# Preamp.net
KiCad netlist of a schematic drawn in Altium Designer
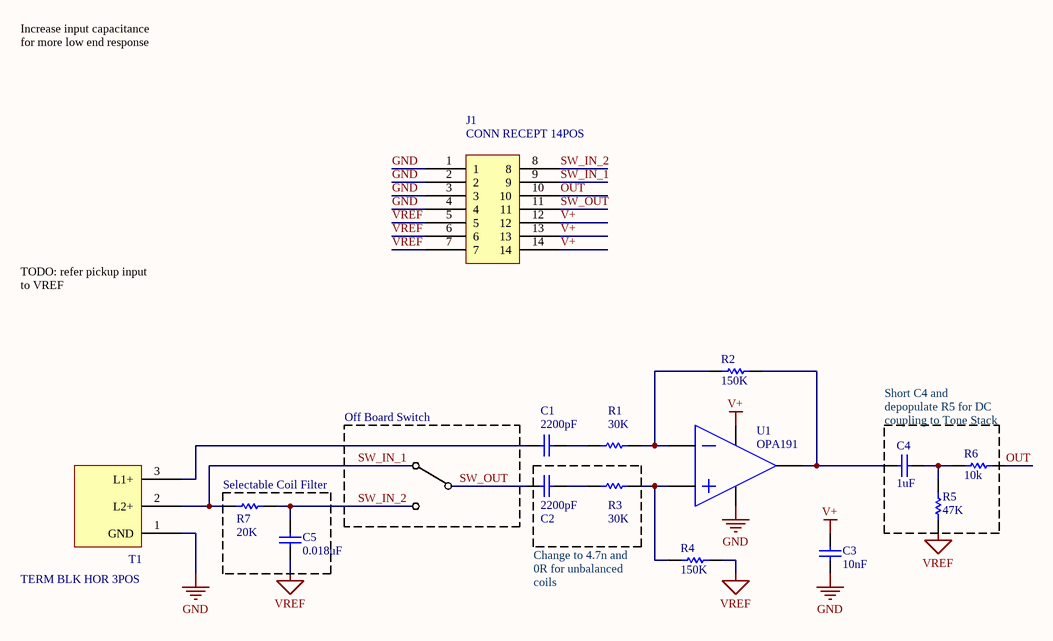
[diagram p0: Preamp.SchDoc]

(export (version "E")
  (design (tool "Eeschema 10.0.6"))
  (components
    (comp (ref "C1")
      (value "2200pF")
      (footprint "CAPC1608X09N")
      (description "2200pF ±1% 50V Ceramic Capacitor C0G, NP0 0603 (1608 Metric)")
      (fields (field (name "DIGIKEY PART NUMBER") "490-7768-1-ND") (field (name "MANUFACTURER") "Murata"))
      (libsource (lib "GuitarLibrary") (part "CAP CER 2200PF 50V C0G/NP0 0603"))
    )
    (comp (ref "C2")
      (value "2200pF")
      (footprint "CAPC1608X09N")
      (description "2200pF ±1% 50V Ceramic Capacitor C0G, NP0 0603 (1608 Metric)")
      (fields (field (name "DIGIKEY PART NUMBER") "490-7768-1-ND") (field (name "MANUFACTURER") "Murata"))
      (libsource (lib "GuitarLibrary") (part "CAP CER 2200PF 50V C0G/NP0 0603"))
    )
    (comp (ref "C3")
      (value "10nF")
      (footprint "CAPC1608X09N")
      (description "10000pF ±5% 50V Ceramic Capacitor C0G, NP0 0603 (1608 Metric)")
      (fields (field (name "DIGIKEY PART NUMBER") "490-9666-1-ND") (field (name "MANUFACTURER") "Murata"))
      (libsource (lib "GuitarLibrary") (part "CAP CER 10000PF 50V C0G/NP0 0603"))
    )
    (comp (ref "C4")
      (value "1uF")
      (footprint "CAPC1608X09N")
      (description "1µF ±10% 25V Ceramic Capacitor X7R 0603 (1608 Metric)")
      (fields (field (name "DIGIKEY PART NUMBER") "490-10673-1-ND") (field (name "VOLTAGE") "25V"))
      (libsource (lib "GuitarLibrary") (part "CAP CER 1UF 25V X7R 0603"))
    )
    (comp (ref "C5")
      (value "0.018uF")
      (footprint "CAPC1608X09N")
      (description "CAP CER 0.018UF 35V NP0 0603")
      (fields (field (name "DIGIKEY PART NUMBER") "445-174558-1-ND") (field (name "VOLTAGE") "35V"))
      (libsource (lib "GuitarLibrary") (part "CAP CER 0.018UF 35V NP0 0603"))
    )
    (comp (ref "J1")
      (value "CONN RECEPT 14POS")
      (footprint "DF12(3.0)-14DS")
      (description "14 Position Connector Header, Outer Shroud Contacts Surface Mount Gold")
      (libsource (lib "GuitarLibrary") (part "DF12(3.0)-14DS-0.5V(86)"))
    )
    (comp (ref "R1")
      (value "30K")
      (footprint "RESC1608X06N")
      (description "RES SMD 30K OHM 1% 1/10W 0603")
      (fields (field (name "TOLERANCE") "1%") (field (name "DIGIKEY PART NUMBER") "311-30.0KHRCT-ND"))
      (libsource (lib "GuitarLibrary") (part "RES SMD 30K OHM 1% 1/10W 0603"))
    )
    (comp (ref "R2")
      (value "150K")
      (footprint "RESC1608X06N")
      (description "RES SMD 150K OHM 1% 1/10W 0603")
      (fields (field (name "TOLERANCE") "1%") (field (name "DIGIKEY PART NUMBER") "311-150KHRCT-ND"))
      (libsource (lib "GuitarLibrary") (part "RES SMD 150K OHM 1% 1/10W 0603"))
    )
    (comp (ref "R3")
      (value "30K")
      (footprint "RESC1608X06N")
      (description "RES SMD 30K OHM 1% 1/10W 0603")
      (fields (field (name "TOLERANCE") "1%") (field (name "DIGIKEY PART NUMBER") "311-30.0KHRCT-ND"))
      (libsource (lib "GuitarLibrary") (part "RES SMD 30K OHM 1% 1/10W 0603"))
    )
    (comp (ref "R4")
      (value "150K")
      (footprint "RESC1608X06N")
      (description "RES SMD 150K OHM 1% 1/10W 0603")
      (fields (field (name "TOLERANCE") "1%") (field (name "DIGIKEY PART NUMBER") "311-150KHRCT-ND"))
      (libsource (lib "GuitarLibrary") (part "RES SMD 150K OHM 1% 1/10W 0603"))
    )
    (comp (ref "R5")
      (value "47K")
      (footprint "RESC1608X06N")
      (description "RES 47K 0603")
      (fields (field (name "TOLERANCE") "1%") (field (name "DIGIKEY PART NUMBER") "311-47.0KHRCT-ND"))
      (libsource (lib "GuitarLibrary") (part "RES SMD 47K OHM 1% 1/10W 0603"))
    )
    (comp (ref "R6")
      (value "10k")
      (footprint "RESC1608X06N")
      (description "RES SMD 10K OHM 1% 1/10W 0603")
      (fields (field (name "TOLERANCE") "1%") (field (name "POWER") "0.1W"))
      (libsource (lib "GuitarLibrary") (part "RES SMD 10K OHM 1% 1/10W 0603"))
    )
    (comp (ref "R7")
      (value "20K")
      (footprint "RESC1608X06N")
      (description "RES SMD 20K OHM 1% 1/10W 0603")
      (fields (field (name "TOLERANCE") "1%") (field (name "DIGIKEY PART NUMBER") "311-20.0KHRCT-ND"))
      (libsource (lib "GuitarLibrary") (part "RES SMD 20K OHM 1% 1/10W 0603"))
    )
    (comp (ref "T1")
      (value "TERM BLK HOR 3POS")
      (footprint "TERM BLK HOR 3POS")
      (description "3 Position Wire to Board Terminal Block Horizontal with Board 0.100\" (2.54mm) Surface Mount")
      (fields (field (name "DIGIKEY PART NUMBER") "1195-3657-1-ND"))
      (libsource (lib "GuitarLibrary") (part "TERM BLK HOR 3POS"))
    )
    (comp (ref "U1")
      (value "OPA191")
      (footprint "SOT23-5")
      (description "General Purpose Amplifier 1 Circuit Rail-to-Rail SOT-23-5")
      (fields (field (name "DIGIKEY PART NUMBER") "296-44386-1-ND"))
      (libsource (lib "GuitarLibrary") (part "OPA191IDBVR"))
    )
  )
  (nets
    (net (code "1") (name "/OUT") (class "Default")
      (node (ref "J1") (pin "10") (pinfunction "10_10") (pintype "passive"))
      (node (ref "R6") (pin "1") (pinfunction "1_1") (pintype "passive"))
    )
    (net (code "2") (name "/SW_IN_1") (class "Default")
      (node (ref "J1") (pin "9") (pinfunction "9_9") (pintype "passive"))
      (node (ref "R7") (pin "1") (pinfunction "1_1") (pintype "passive"))
      (node (ref "T1") (pin "2") (pinfunction "L2+_2") (pintype "passive"))
    )
    (net (code "3") (name "/SW_IN_2") (class "Default")
      (node (ref "C5") (pin "2") (pinfunction "2_2") (pintype "passive"))
      (node (ref "J1") (pin "8") (pinfunction "8_8") (pintype "passive"))
      (node (ref "R7") (pin "2") (pinfunction "2_2") (pintype "passive"))
    )
    (net (code "4") (name "/SW_OUT") (class "Default")
      (node (ref "C2") (pin "1") (pinfunction "1_1") (pintype "passive"))
      (node (ref "J1") (pin "11") (pinfunction "11_11") (pintype "passive"))
    )
    (net (code "5") (name "GND") (class "Default")
      (node (ref "C3") (pin "1") (pinfunction "1_1") (pintype "passive"))
      (node (ref "J1") (pin "1") (pinfunction "1_1") (pintype "passive"))
      (node (ref "J1") (pin "2") (pinfunction "2_2") (pintype "passive"))
      (node (ref "J1") (pin "3") (pinfunction "3_3") (pintype "passive"))
      (node (ref "J1") (pin "4") (pinfunction "4_4") (pintype "passive"))
      (node (ref "T1") (pin "1") (pinfunction "GND_1") (pintype "passive"))
      (node (ref "U1") (pin "2") (pinfunction "GND_2") (pintype "power_in"))
    )
    (net (code "6") (name "Net-(C1-Pad2)") (class "Default")
      (node (ref "C1") (pin "2") (pinfunction "2_2") (pintype "passive"))
      (node (ref "R1") (pin "1") (pinfunction "1_1") (pintype "passive"))
    )
    (net (code "7") (name "Net-(C2-Pad2)") (class "Default")
      (node (ref "C2") (pin "2") (pinfunction "2_2") (pintype "passive"))
      (node (ref "R3") (pin "1") (pinfunction "1_1") (pintype "passive"))
    )
    (net (code "8") (name "Net-(C4-Pad2)") (class "Default")
      (node (ref "C4") (pin "2") (pinfunction "2_2") (pintype "passive"))
      (node (ref "R5") (pin "2") (pinfunction "2_2") (pintype "passive"))
      (node (ref "R6") (pin "2") (pinfunction "2_2") (pintype "passive"))
    )
    (net (code "9") (name "Net-(T1-L1+)") (class "Default")
      (node (ref "C1") (pin "1") (pinfunction "1_1") (pintype "passive"))
      (node (ref "T1") (pin "3") (pinfunction "L1+_3") (pintype "passive"))
    )
    (net (code "10") (name "Net-(U1-VIN+)") (class "Default")
      (node (ref "R3") (pin "2") (pinfunction "2_2") (pintype "passive"))
      (node (ref "R4") (pin "1") (pinfunction "1_1") (pintype "passive"))
      (node (ref "U1") (pin "3") (pinfunction "VIN+_3") (pintype "passive"))
    )
    (net (code "11") (name "Net-(U1-VIN-)") (class "Default")
      (node (ref "R1") (pin "2") (pinfunction "2_2") (pintype "passive"))
      (node (ref "R2") (pin "1") (pinfunction "1_1") (pintype "passive"))
      (node (ref "U1") (pin "4") (pinfunction "VIN-_4") (pintype "passive"))
    )
    (net (code "12") (name "Net-(U1-VOUT)") (class "Default")
      (node (ref "C4") (pin "1") (pinfunction "1_1") (pintype "passive"))
      (node (ref "R2") (pin "2") (pinfunction "2_2") (pintype "passive"))
      (node (ref "U1") (pin "1") (pinfunction "VOUT_1") (pintype "passive"))
    )
    (net (code "13") (name "V+") (class "Default")
      (node (ref "C3") (pin "2") (pinfunction "2_2") (pintype "passive"))
      (node (ref "J1") (pin "12") (pinfunction "12_12") (pintype "passive"))
      (node (ref "J1") (pin "13") (pinfunction "13_13") (pintype "passive"))
      (node (ref "J1") (pin "14") (pinfunction "14_14") (pintype "passive"))
      (node (ref "U1") (pin "5") (pinfunction "V+_5") (pintype "power_in"))
    )
    (net (code "14") (name "VREF") (class "Default")
      (node (ref "C5") (pin "1") (pinfunction "1_1") (pintype "passive"))
      (node (ref "J1") (pin "5") (pinfunction "5_5") (pintype "passive"))
      (node (ref "J1") (pin "6") (pinfunction "6_6") (pintype "passive"))
      (node (ref "J1") (pin "7") (pinfunction "7_7") (pintype "passive"))
      (node (ref "R4") (pin "2") (pinfunction "2_2") (pintype "passive"))
      (node (ref "R5") (pin "1") (pinfunction "1_1") (pintype "passive"))
    )
  )
)
